# BH_Pzem_WI_FI_SHIELD.net
KiCad netlist of a schematic drawn in EAGLE
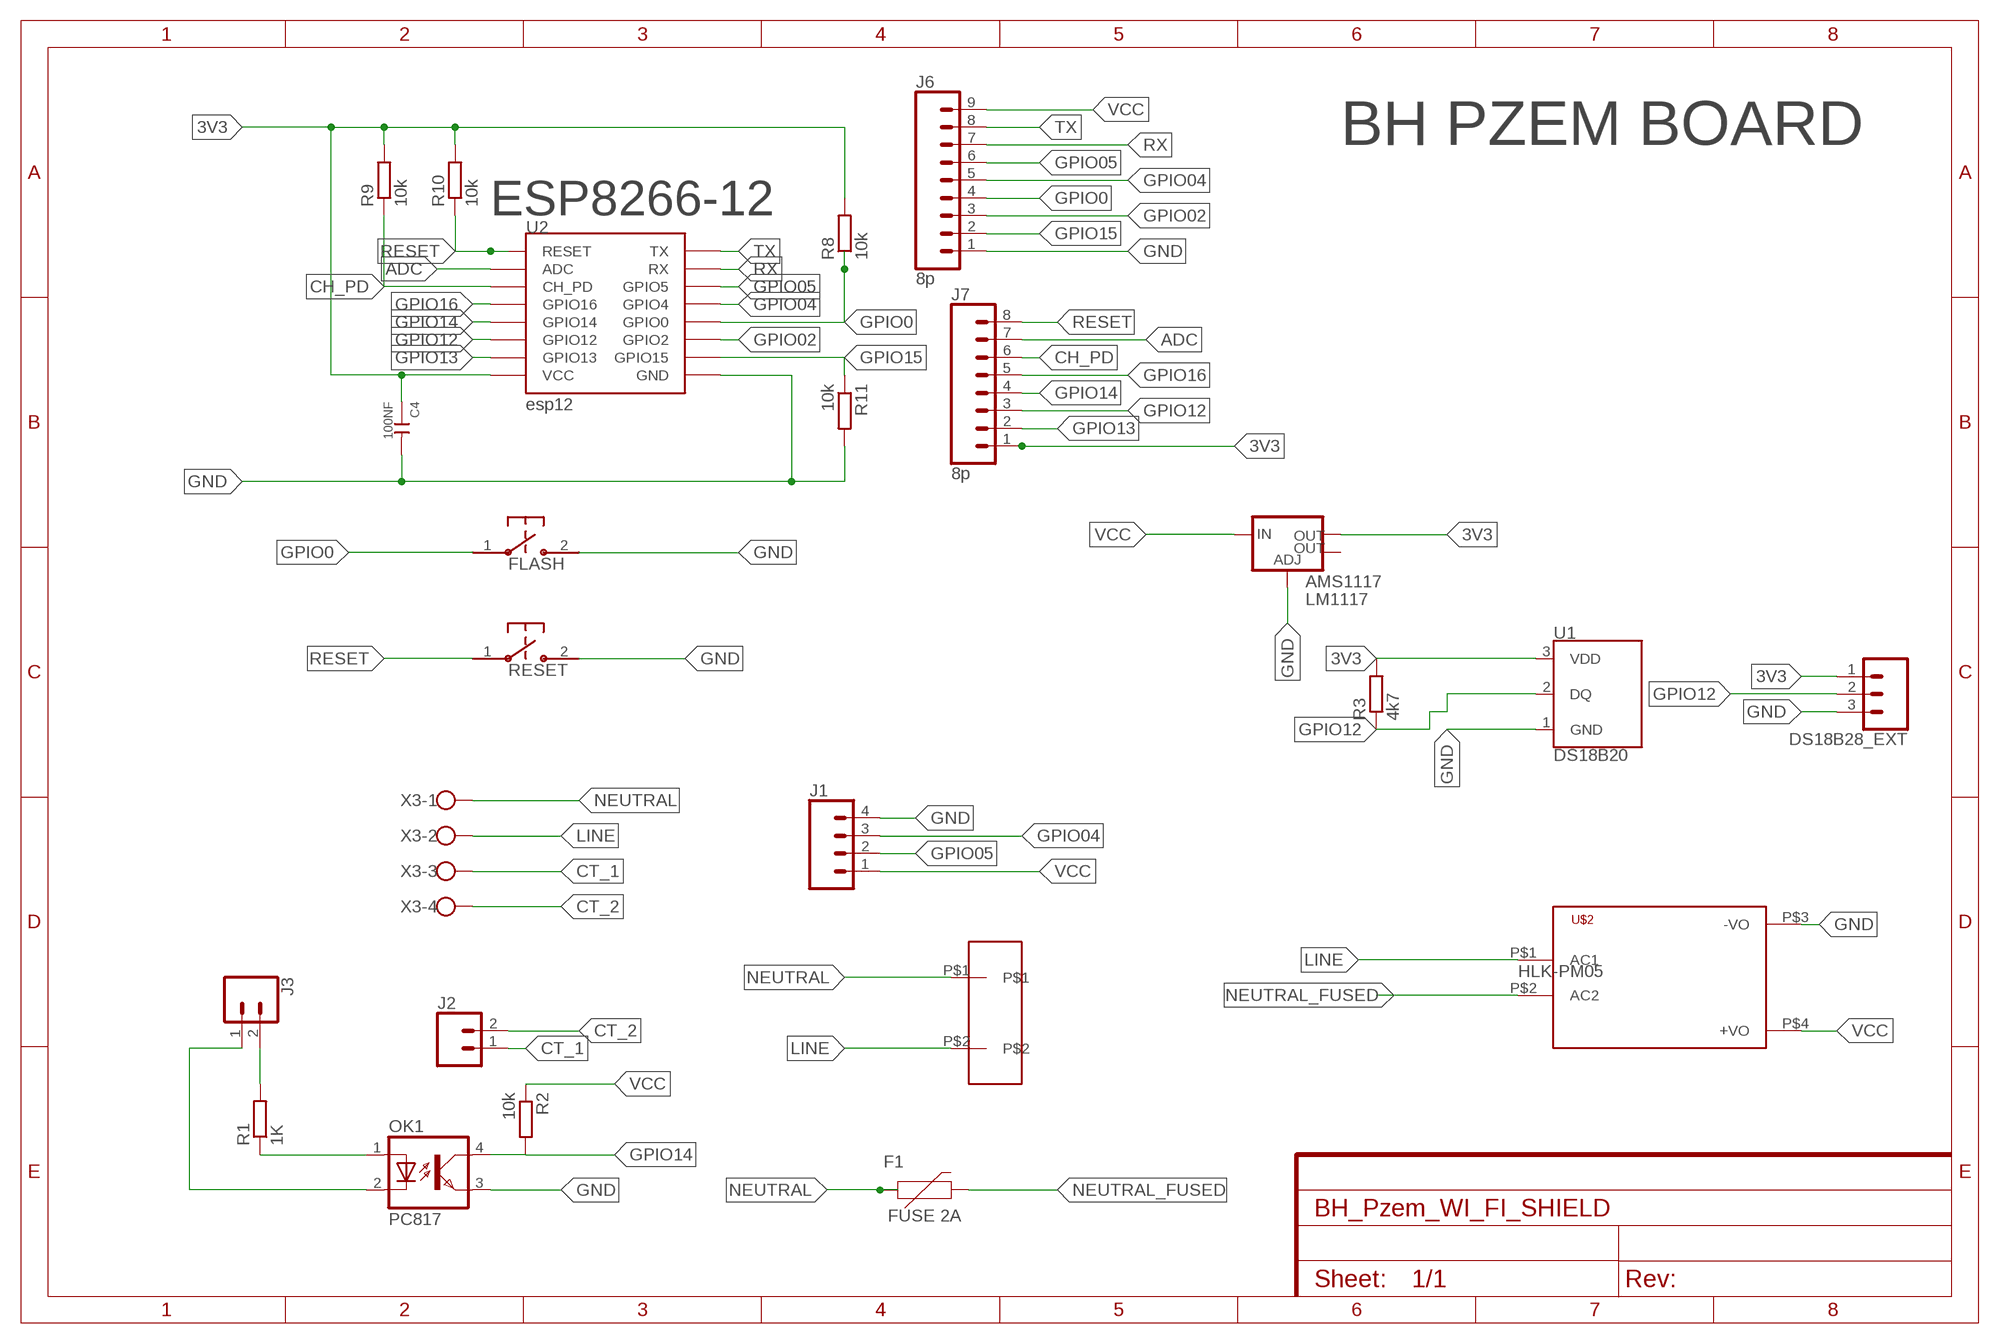
[diagram p0: schematic, sheet 1]

(export (version "E")
  (design (tool "Eeschema 10.0.6"))
  (components
    (comp (ref "AMS1117")
      (value "LM1117")
      (footprint "eagle-import:SOT223")
      (libsource (lib "eagle-import") (part "V_REG_LM1117SOT223"))
    )
    (comp (ref "C4")
      (value "100NF")
      (footprint "eagle-import:C1206")
      (fields (field (name "MPN") "CC1206KKX7RCBB102"))
      (libsource (lib "eagle-import") (part "CERAMIC-1NF-1KV-10%-X7R?(1206)"))
    )
    (comp (ref "DS18B28_EXT")
      (value "CONN_03")
      (footprint "eagle-import:1X03")
      (libsource (lib "eagle-import") (part "CONN_03"))
    )
    (comp (ref "F1")
      (value "FUSE 2A")
      (footprint "eagle-import:PTH")
      (libsource (lib "eagle-import") (part "PPTC_PTH"))
    )
    (comp (ref "FLASH")
      (value "B3U-1000P-2P-SMD")
      (footprint "eagle-import:B3U-1000P")
      (fields
        (field (name "MANUFACTURER") "Omron")
        (field (name "MPN") "B3U-1000P")
        (field (name "SPICEPREFIX") "F")
      )
      (libsource (lib "eagle-import") (part "B3U-1000P"))
    )
    (comp (ref "J1")
      (value "CONN_04")
      (footprint "eagle-import:1X04")
      (libsource (lib "eagle-import") (part "CONN_04"))
    )
    (comp (ref "J2")
      (value "CONN_02")
      (footprint "eagle-import:1X02")
      (libsource (lib "eagle-import") (part "CONN_02"))
    )
    (comp (ref "J3")
      (value "CONN_02")
      (footprint "eagle-import:1X02")
      (libsource (lib "eagle-import") (part "CONN_02"))
    )
    (comp (ref "J6")
      (value "8p")
      (footprint "eagle-import:1X09")
      (libsource (lib "eagle-import") (part "CONN_09"))
    )
    (comp (ref "J7")
      (value "8p")
      (footprint "eagle-import:1X08")
      (libsource (lib "eagle-import") (part "CONN_08{dblquote}"))
    )
    (comp (ref "OK1")
      (value "PC817")
      (footprint "eagle-import:DIL04")
      (fields (field (name "MPN") "PC817X4J000F"))
      (libsource (lib "eagle-import") (part "PC817"))
    )
    (comp (ref "R1")
      (value "1K")
      (footprint "eagle-import:R0603")
      (libsource (lib "eagle-import") (part "R-EU_R0603"))
    )
    (comp (ref "R2")
      (value "10k")
      (footprint "eagle-import:R0603")
      (libsource (lib "eagle-import") (part "R-EU_R0603"))
    )
    (comp (ref "R3")
      (value "4k7")
      (footprint "eagle-import:R0603")
      (libsource (lib "eagle-import") (part "R-EU_R0603"))
    )
    (comp (ref "R8")
      (value "10k")
      (footprint "eagle-import:R0603")
      (libsource (lib "eagle-import") (part "R-EU_R0603"))
    )
    (comp (ref "R9")
      (value "10k")
      (footprint "eagle-import:R0603")
      (libsource (lib "eagle-import") (part "R-EU_R0603"))
    )
    (comp (ref "R10")
      (value "10k")
      (footprint "eagle-import:R0603")
      (libsource (lib "eagle-import") (part "R-EU_R0603"))
    )
    (comp (ref "R11")
      (value "10k")
      (footprint "eagle-import:R0603")
      (libsource (lib "eagle-import") (part "R-EU_R0603"))
    )
    (comp (ref "RESET")
      (value "B3U-1000P-2P-SMD")
      (footprint "eagle-import:B3U-1000P")
      (fields (field (name "MANUFACTURER") "Omron") (field (name "MPN") "B3U-1000P"))
      (libsource (lib "eagle-import") (part "B3U-1000P"))
    )
    (comp (ref "U$1")
      (value "SCREWTERMINALS_5MM_2")
      (footprint "eagle-import:TERMINAL_2X")
      (libsource (lib "eagle-import") (part "SCREWTERMINALS_5MM_2"))
    )
    (comp (ref "U$2")
      (value "HKLPM01")
      (footprint "eagle-import:HKLPM01")
      (libsource (lib "eagle-import") (part "HKLPM01"))
    )
    (comp (ref "U1")
      (value "DS18B20")
      (footprint "eagle-import:TO-92-AMMO")
      (libsource (lib "eagle-import") (part "DS18B20"))
    )
    (comp (ref "U2")
      (value "esp12")
      (footprint "eagle-import:ESP12-SMD")
      (libsource (lib "eagle-import") (part "ESP12SMD"))
    )
    (comp (ref "X3")
      (value "W237-4")
      (footprint "eagle-import:W237-4")
      (libsource (lib "eagle-import") (part "W237-4"))
    )
  )
  (nets
    (net (code "1") (name "3V3") (class "Default")
      (node (ref "AMS1117") (pin "2") (pinfunction "OUT_2") (pintype "output"))
      (node (ref "C4") (pin "1") (pinfunction "1_1") (pintype "passive"))
      (node (ref "DS18B28_EXT") (pin "1") (pinfunction "1_1") (pintype "passive"))
      (node (ref "J7") (pin "1") (pinfunction "1_1") (pintype "passive"))
      (node (ref "R10") (pin "2") (pinfunction "2_2") (pintype "passive"))
      (node (ref "R3") (pin "2") (pinfunction "2_2") (pintype "passive"))
      (node (ref "R8") (pin "2") (pinfunction "2_2") (pintype "passive"))
      (node (ref "R9") (pin "2") (pinfunction "2_2") (pintype "passive"))
      (node (ref "U1") (pin "3") (pinfunction "VDD_3") (pintype "power_in"))
      (node (ref "U2") (pin "VCC") (pinfunction "VCC_VCC") (pintype "bidirectional"))
    )
    (net (code "2") (name "ADC") (class "Default")
      (node (ref "J7") (pin "7") (pinfunction "7_7") (pintype "passive"))
      (node (ref "U2") (pin "ADC") (pinfunction "ADC_ADC") (pintype "bidirectional"))
    )
    (net (code "3") (name "CH_PD") (class "Default")
      (node (ref "J7") (pin "6") (pinfunction "6_6") (pintype "passive"))
      (node (ref "R9") (pin "1") (pinfunction "1_1") (pintype "passive"))
      (node (ref "U2") (pin "CH_PD") (pinfunction "CH_PD_CH_PD") (pintype "bidirectional"))
    )
    (net (code "4") (name "CT_1") (class "Default")
      (node (ref "J2") (pin "1") (pinfunction "1_1") (pintype "passive"))
      (node (ref "X3") (pin "3") (pinfunction "KL_3") (pintype "passive"))
    )
    (net (code "5") (name "CT_2") (class "Default")
      (node (ref "J2") (pin "2") (pinfunction "2_2") (pintype "passive"))
      (node (ref "X3") (pin "4") (pinfunction "KL_4") (pintype "passive"))
    )
    (net (code "6") (name "GND") (class "Default")
      (node (ref "AMS1117") (pin "1") (pinfunction "ADJ_1") (pintype "input"))
      (node (ref "C4") (pin "2") (pinfunction "2_2") (pintype "passive"))
      (node (ref "DS18B28_EXT") (pin "3") (pinfunction "3_3") (pintype "passive"))
      (node (ref "FLASH") (pin "2") (pinfunction "P$2_2") (pintype "passive"))
      (node (ref "J1") (pin "4") (pinfunction "4_4") (pintype "passive"))
      (node (ref "J6") (pin "1") (pinfunction "1_1") (pintype "passive"))
      (node (ref "OK1") (pin "3") (pinfunction "EMIT_3") (pintype "passive"))
      (node (ref "R11") (pin "2") (pinfunction "2_2") (pintype "passive"))
      (node (ref "RESET") (pin "2") (pinfunction "P$2_2") (pintype "passive"))
      (node (ref "U$2") (pin "P$3") (pinfunction "-VO_P$3") (pintype "bidirectional"))
      (node (ref "U1") (pin "1") (pinfunction "GND_1") (pintype "power_in"))
      (node (ref "U2") (pin "GND") (pinfunction "GND_GND") (pintype "bidirectional"))
    )
    (net (code "7") (name "GPIO0") (class "Default")
      (node (ref "FLASH") (pin "1") (pinfunction "P$1_1") (pintype "passive"))
      (node (ref "J6") (pin "4") (pinfunction "4_4") (pintype "passive"))
      (node (ref "R8") (pin "1") (pinfunction "1_1") (pintype "passive"))
      (node (ref "U2") (pin "GPIO0") (pinfunction "GPIO0_GPIO0") (pintype "bidirectional"))
    )
    (net (code "8") (name "GPIO02") (class "Default")
      (node (ref "J6") (pin "3") (pinfunction "3_3") (pintype "passive"))
      (node (ref "U2") (pin "GPIO2") (pinfunction "GPIO2_GPIO2") (pintype "bidirectional"))
    )
    (net (code "9") (name "GPIO04") (class "Default")
      (node (ref "J1") (pin "3") (pinfunction "3_3") (pintype "passive"))
      (node (ref "J6") (pin "5") (pinfunction "5_5") (pintype "passive"))
      (node (ref "U2") (pin "GPIO4") (pinfunction "GPIO4_GPIO4") (pintype "bidirectional"))
    )
    (net (code "10") (name "GPIO05") (class "Default")
      (node (ref "J1") (pin "2") (pinfunction "2_2") (pintype "passive"))
      (node (ref "J6") (pin "6") (pinfunction "6_6") (pintype "passive"))
      (node (ref "U2") (pin "GPIO5") (pinfunction "GPIO5_GPIO5") (pintype "bidirectional"))
    )
    (net (code "11") (name "GPIO12") (class "Default")
      (node (ref "DS18B28_EXT") (pin "2") (pinfunction "2_2") (pintype "passive"))
      (node (ref "J7") (pin "3") (pinfunction "3_3") (pintype "passive"))
      (node (ref "R3") (pin "1") (pinfunction "1_1") (pintype "passive"))
      (node (ref "U1") (pin "2") (pinfunction "DQ_2") (pintype "bidirectional"))
      (node (ref "U2") (pin "GPIO12") (pinfunction "GPIO12_GPIO12") (pintype "bidirectional"))
    )
    (net (code "12") (name "GPIO13") (class "Default")
      (node (ref "J7") (pin "2") (pinfunction "2_2") (pintype "passive"))
      (node (ref "U2") (pin "GPIO13") (pinfunction "GPIO13_GPIO13") (pintype "bidirectional"))
    )
    (net (code "13") (name "GPIO14") (class "Default")
      (node (ref "J7") (pin "4") (pinfunction "4_4") (pintype "passive"))
      (node (ref "OK1") (pin "4") (pinfunction "COL_4") (pintype "passive"))
      (node (ref "R2") (pin "2") (pinfunction "2_2") (pintype "passive"))
      (node (ref "U2") (pin "GPIO14") (pinfunction "GPIO14_GPIO14") (pintype "bidirectional"))
    )
    (net (code "14") (name "GPIO15") (class "Default")
      (node (ref "J6") (pin "2") (pinfunction "2_2") (pintype "passive"))
      (node (ref "R11") (pin "1") (pinfunction "1_1") (pintype "passive"))
      (node (ref "U2") (pin "GPIO15") (pinfunction "GPIO15_GPIO15") (pintype "bidirectional"))
    )
    (net (code "15") (name "GPIO16") (class "Default")
      (node (ref "J7") (pin "5") (pinfunction "5_5") (pintype "passive"))
      (node (ref "U2") (pin "GPIO16") (pinfunction "GPIO16_GPIO16") (pintype "bidirectional"))
    )
    (net (code "16") (name "LINE") (class "Default")
      (node (ref "U$1") (pin "P$2") (pinfunction "P$2_P$2") (pintype "bidirectional"))
      (node (ref "U$2") (pin "P$1") (pinfunction "AC1_P$1") (pintype "bidirectional"))
      (node (ref "X3") (pin "2") (pinfunction "KL_2") (pintype "passive"))
    )
    (net (code "17") (name "NEUTRAL") (class "Default")
      (node (ref "F1") (pin "P$1") (pinfunction "1_P$1") (pintype "bidirectional"))
      (node (ref "U$1") (pin "P$1") (pinfunction "P$1_P$1") (pintype "bidirectional"))
      (node (ref "X3") (pin "1") (pinfunction "KL_1") (pintype "passive"))
    )
    (net (code "18") (name "NEUTRAL_FUSED") (class "Default")
      (node (ref "F1") (pin "P$2") (pinfunction "2_P$2") (pintype "bidirectional"))
      (node (ref "U$2") (pin "P$2") (pinfunction "AC2_P$2") (pintype "bidirectional"))
    )
    (net (code "19") (name "Net-(J3-Pad2)") (class "Default")
      (node (ref "J3") (pin "2") (pinfunction "2_2") (pintype "passive"))
      (node (ref "R1") (pin "2") (pinfunction "2_2") (pintype "passive"))
    )
    (net (code "20") (name "Net-(OK1-A)") (class "Default")
      (node (ref "OK1") (pin "1") (pinfunction "A_1") (pintype "passive"))
      (node (ref "R1") (pin "1") (pinfunction "1_1") (pintype "passive"))
    )
    (net (code "21") (name "Net-(OK1-C)") (class "Default")
      (node (ref "J3") (pin "1") (pinfunction "1_1") (pintype "passive"))
      (node (ref "OK1") (pin "2") (pinfunction "C_2") (pintype "passive"))
    )
    (net (code "22") (name "RESET") (class "Default")
      (node (ref "J7") (pin "8") (pinfunction "8_8") (pintype "passive"))
      (node (ref "R10") (pin "1") (pinfunction "1_1") (pintype "passive"))
      (node (ref "RESET") (pin "1") (pinfunction "P$1_1") (pintype "passive"))
      (node (ref "U2") (pin "RESET") (pinfunction "RESET_RESET") (pintype "bidirectional"))
    )
    (net (code "23") (name "RX") (class "Default")
      (node (ref "J6") (pin "7") (pinfunction "7_7") (pintype "passive"))
      (node (ref "U2") (pin "RXD0") (pinfunction "RX_RXD0") (pintype "bidirectional"))
    )
    (net (code "24") (name "TX") (class "Default")
      (node (ref "J6") (pin "8") (pinfunction "8_8") (pintype "passive"))
      (node (ref "U2") (pin "TXD0") (pinfunction "TX_TXD0") (pintype "bidirectional"))
    )
    (net (code "25") (name "VCC") (class "Default")
      (node (ref "AMS1117") (pin "3") (pinfunction "IN_3") (pintype "input"))
      (node (ref "J1") (pin "1") (pinfunction "1_1") (pintype "passive"))
      (node (ref "J6") (pin "9") (pinfunction "9_9") (pintype "passive"))
      (node (ref "R2") (pin "1") (pinfunction "1_1") (pintype "passive"))
      (node (ref "U$2") (pin "P$4") (pinfunction "+VO_P$4") (pintype "bidirectional"))
    )
    (net (code "26") (name "unconnected-(AMS1117-OUT-Pad4)") (class "Default")
      (node (ref "AMS1117") (pin "4") (pinfunction "OUT_4") (pintype "output"))
    )
  )
)
